# segger_adaptor_v1.net
KiCad netlist of a schematic drawn in EAGLE
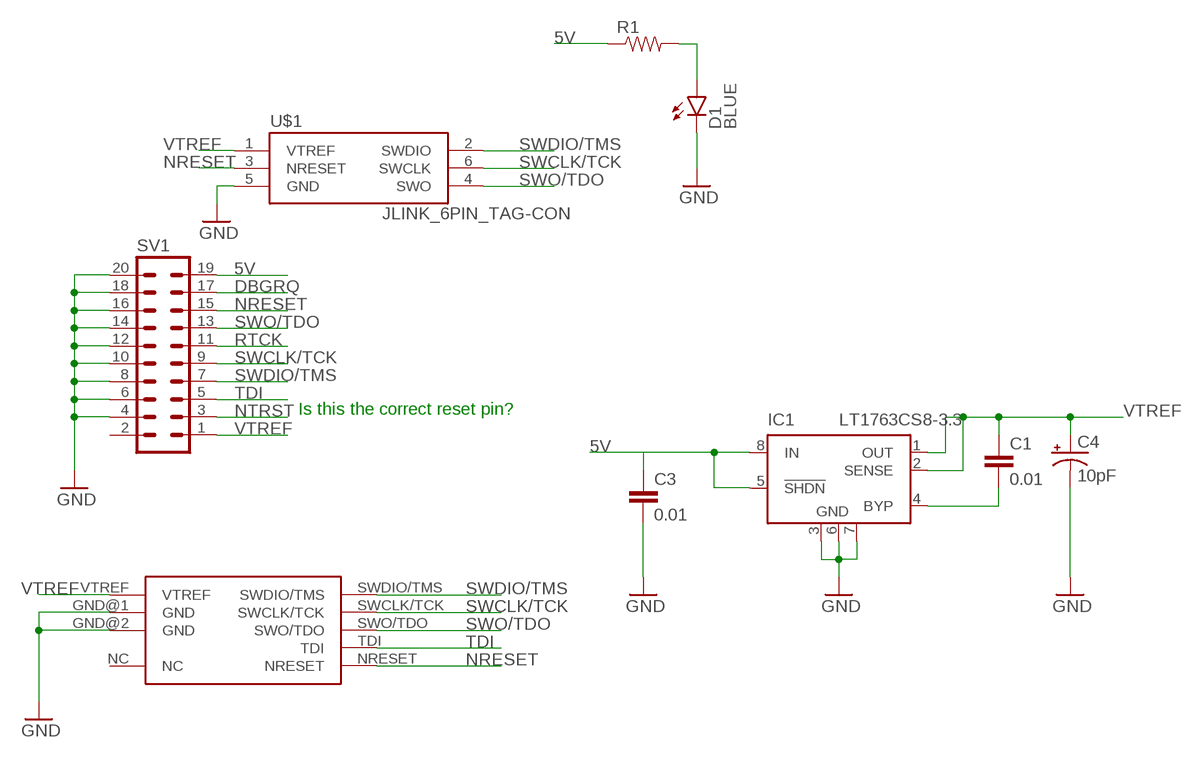
[diagram p0: schematic, sheet 1]

(export (version "E")
  (design (tool "Eeschema 10.0.6"))
  (components
    (comp (ref "C1")
      (value "0.01")
      (footprint "eagle-import:C0603")
      (libsource (lib "eagle-import") (part "C-EUC0603"))
    )
    (comp (ref "C3")
      (value "0.01")
      (footprint "eagle-import:C0603")
      (libsource (lib "eagle-import") (part "C-EUC0603"))
    )
    (comp (ref "C4")
      (value "10pF")
      (footprint "eagle-import:EIA3216")
      (libsource (lib "eagle-import") (part "CAP_POL1206"))
    )
    (comp (ref "D1")
      (value "BLUE")
      (footprint "eagle-import:LED-0603")
      (libsource (lib "eagle-import") (part "LED-BLUE0603"))
    )
    (comp (ref "IC1")
      (value "LT1763CS8-3.3")
      (footprint "eagle-import:SOIC8")
      (libsource (lib "eagle-import") (part "LT1763CS8-3.3"))
    )
    (comp (ref "R1")
      (value "RESISTOR0402-RES")
      (footprint "eagle-import:0402-RES")
      (libsource (lib "eagle-import") (part "RESISTOR0402-RES"))
    )
    (comp (ref "SV1")
      (value "ML20")
      (footprint "eagle-import:ML20")
      (libsource (lib "eagle-import") (part "ML20"))
    )
    (comp (ref "U$1")
      (value "JLINK_6PIN_TAG-CON")
      (footprint "eagle-import:2X3_MALE_SHROUDED_0.100")
      (libsource (lib "eagle-import") (part "JLINK_6PIN_TAG-CON"))
    )
    (comp (ref "U$2")
      (value "PINHD-2X3/0.050")
      (footprint "eagle-import:2X10-0.050")
      (libsource (lib "eagle-import") (part "PINHD-2X3/0.050"))
    )
  )
  (nets
    (net (code "1") (name "/5V") (class "Default")
      (node (ref "C3") (pin "1") (pinfunction "1_1") (pintype "passive"))
      (node (ref "IC1") (pin "5") (pinfunction "~{SHDN}_5") (pintype "input"))
      (node (ref "IC1") (pin "8") (pinfunction "IN_8") (pintype "input"))
      (node (ref "R1") (pin "1") (pinfunction "1_1") (pintype "passive"))
      (node (ref "SV1") (pin "19") (pinfunction "19_19") (pintype "passive"))
    )
    (net (code "2") (name "/DBGRQ") (class "Default")
      (node (ref "SV1") (pin "17") (pinfunction "17_17") (pintype "passive"))
    )
    (net (code "3") (name "/NRESET") (class "Default")
      (node (ref "SV1") (pin "15") (pinfunction "15_15") (pintype "passive"))
      (node (ref "U$1") (pin "3") (pinfunction "NRESET_3") (pintype "bidirectional"))
      (node (ref "U$2") (pin "NRESET") (pinfunction "NRESET_NRESET") (pintype "bidirectional"))
    )
    (net (code "4") (name "/NTRST") (class "Default")
      (node (ref "SV1") (pin "3") (pinfunction "3_3") (pintype "passive"))
    )
    (net (code "5") (name "/RTCK") (class "Default")
      (node (ref "SV1") (pin "11") (pinfunction "11_11") (pintype "passive"))
    )
    (net (code "6") (name "/SWCLK{slash}TCK") (class "Default")
      (node (ref "SV1") (pin "9") (pinfunction "9_9") (pintype "passive"))
      (node (ref "U$1") (pin "6") (pinfunction "SWCLK_6") (pintype "bidirectional"))
      (node (ref "U$2") (pin "SWCLK/TCK") (pinfunction "SWCLK/TCK_SWCLK/TCK") (pintype "bidirectional"))
    )
    (net (code "7") (name "/SWDIO{slash}TMS") (class "Default")
      (node (ref "SV1") (pin "7") (pinfunction "7_7") (pintype "passive"))
      (node (ref "U$1") (pin "2") (pinfunction "SWDIO_2") (pintype "bidirectional"))
      (node (ref "U$2") (pin "SWDIO/TMS") (pinfunction "SWDIO/TMS_SWDIO/TMS") (pintype "bidirectional"))
    )
    (net (code "8") (name "/SWO{slash}TDO") (class "Default")
      (node (ref "SV1") (pin "13") (pinfunction "13_13") (pintype "passive"))
      (node (ref "U$1") (pin "4") (pinfunction "SWO_4") (pintype "bidirectional"))
      (node (ref "U$2") (pin "SWO/TDO") (pinfunction "SWO/TDO_SWO/TDO") (pintype "bidirectional"))
    )
    (net (code "9") (name "/TDI") (class "Default")
      (node (ref "SV1") (pin "5") (pinfunction "5_5") (pintype "passive"))
      (node (ref "U$2") (pin "TDI") (pinfunction "TDI_TDI") (pintype "bidirectional"))
    )
    (net (code "10") (name "/VTREF") (class "Default")
      (node (ref "C1") (pin "1") (pinfunction "1_1") (pintype "passive"))
      (node (ref "C4") (pin "A") (pinfunction "+_A") (pintype "passive"))
      (node (ref "IC1") (pin "1") (pinfunction "OUT_1") (pintype "passive"))
      (node (ref "IC1") (pin "2") (pinfunction "SENSE_2") (pintype "input"))
      (node (ref "SV1") (pin "1") (pinfunction "1_1") (pintype "passive"))
      (node (ref "U$1") (pin "1") (pinfunction "VTREF_1") (pintype "bidirectional"))
      (node (ref "U$2") (pin "VTREF") (pinfunction "VTREF_VTREF") (pintype "bidirectional"))
    )
    (net (code "11") (name "GND") (class "Default")
      (node (ref "C3") (pin "2") (pinfunction "2_2") (pintype "passive"))
      (node (ref "C4") (pin "C") (pinfunction "-_C") (pintype "passive"))
      (node (ref "D1") (pin "C") (pinfunction "C_C") (pintype "passive"))
      (node (ref "IC1") (pin "3") (pinfunction "GND_3") (pintype "power_in"))
      (node (ref "IC1") (pin "6") (pinfunction "GND_6") (pintype "power_in"))
      (node (ref "IC1") (pin "7") (pinfunction "GND_7") (pintype "power_in"))
      (node (ref "SV1") (pin "10") (pinfunction "10_10") (pintype "passive"))
      (node (ref "SV1") (pin "12") (pinfunction "12_12") (pintype "passive"))
      (node (ref "SV1") (pin "14") (pinfunction "14_14") (pintype "passive"))
      (node (ref "SV1") (pin "16") (pinfunction "16_16") (pintype "passive"))
      (node (ref "SV1") (pin "18") (pinfunction "18_18") (pintype "passive"))
      (node (ref "SV1") (pin "20") (pinfunction "20_20") (pintype "passive"))
      (node (ref "SV1") (pin "4") (pinfunction "4_4") (pintype "passive"))
      (node (ref "SV1") (pin "6") (pinfunction "6_6") (pintype "passive"))
      (node (ref "SV1") (pin "8") (pinfunction "8_8") (pintype "passive"))
      (node (ref "U$1") (pin "5") (pinfunction "GND_5") (pintype "bidirectional"))
      (node (ref "U$2") (pin "GND@1") (pinfunction "GND_GND@1") (pintype "bidirectional"))
      (node (ref "U$2") (pin "GND@2") (pinfunction "GND_GND@2") (pintype "bidirectional"))
    )
    (net (code "12") (name "Net-(D1-PadA)") (class "Default")
      (node (ref "D1") (pin "A") (pinfunction "A_A") (pintype "passive"))
      (node (ref "R1") (pin "2") (pinfunction "2_2") (pintype "passive"))
    )
    (net (code "13") (name "Net-(IC1-BYP)") (class "Default")
      (node (ref "C1") (pin "2") (pinfunction "2_2") (pintype "passive"))
      (node (ref "IC1") (pin "4") (pinfunction "BYP_4") (pintype "input"))
    )
    (net (code "14") (name "unconnected-(SV1-Pad2)") (class "Default")
      (node (ref "SV1") (pin "2") (pinfunction "2_2") (pintype "passive"))
    )
    (net (code "15") (name "unconnected-(U$2-PadNC)") (class "Default")
      (node (ref "U$2") (pin "NC") (pinfunction "NC_NC") (pintype "bidirectional"))
    )
  )
)
